# Sheet2.net
KiCad netlist of a schematic drawn in Altium Designer
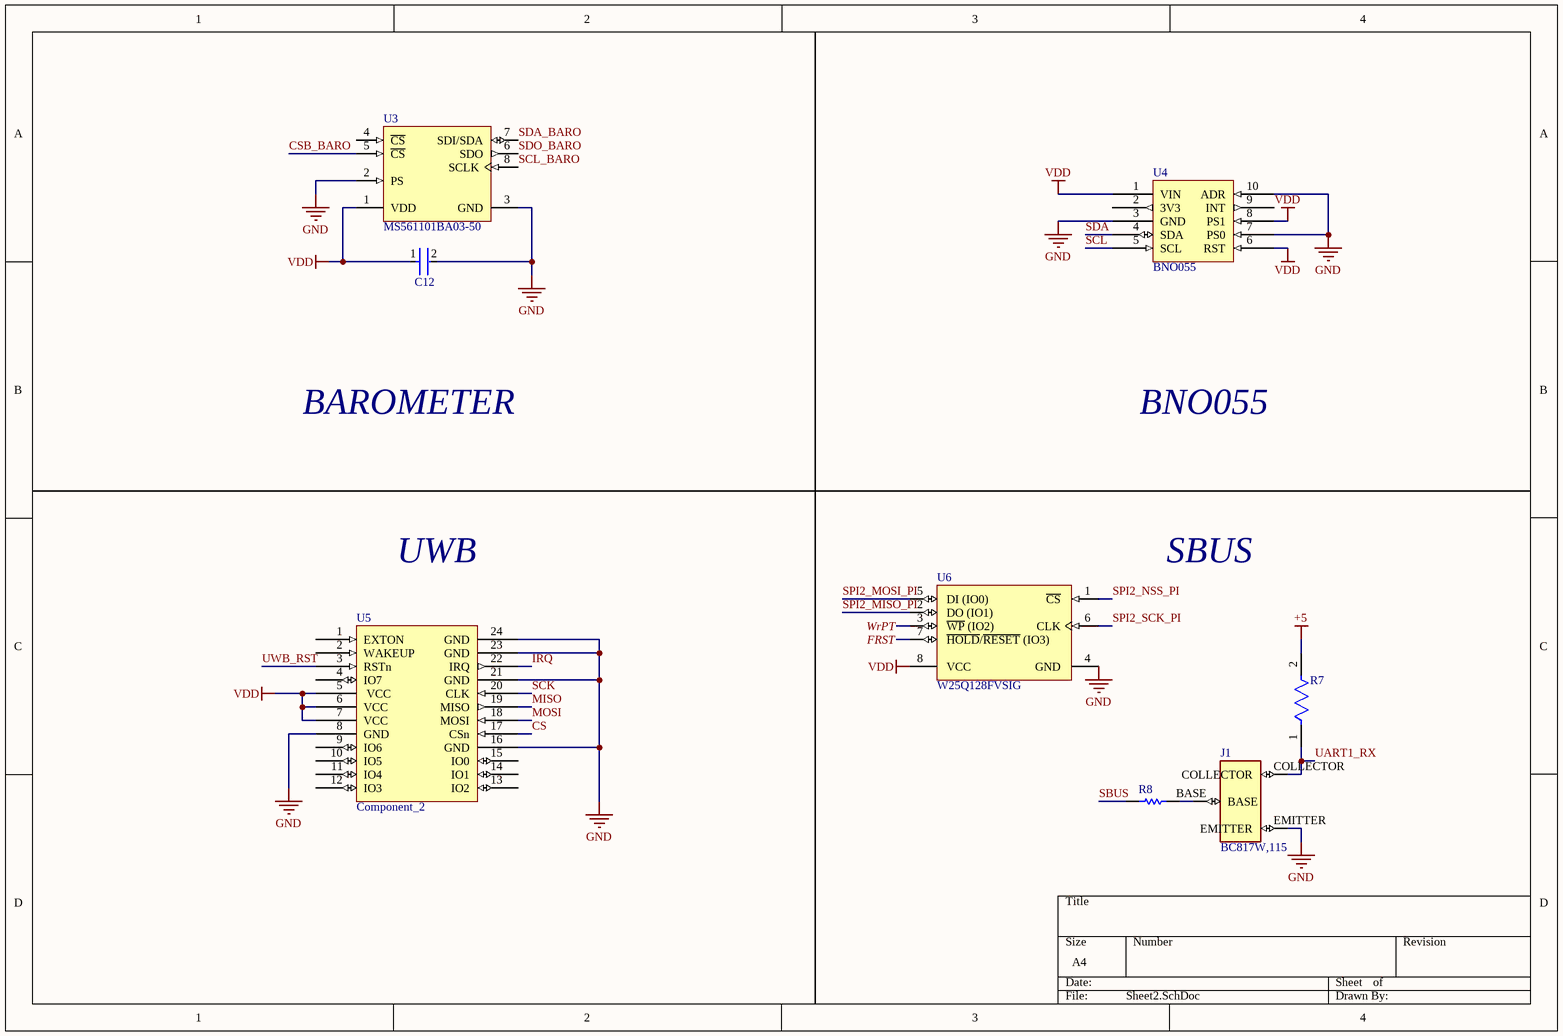
[diagram p0: Sheet2.SchDoc]

(export (version "E")
  (design (tool "Eeschema 10.0.6"))
  (components
    (comp (ref "C12")
      (value "C0603C104K4RACTU")
      (footprint "FP-C0603C-CF-MFG")
      (description "Capacitor; Ceramic; Cap; .100uF; Tol 10%; SMT; Vol-Rtg 16V; X7R; Tape and Reel")
      (fields
        (field (name "OCTOPART") "https://octopart.com/c0603c104k4ractu-kemet-93067")
        (field (name "MANUFACTURER") "KEMET")
      )
      (libsource (lib "Altium Content Vault") (part "b4654b650e69147ec39a6b967a45e02"))
    )
    (comp (ref "J1")
      (value "BC817W,115")
      (footprint "SOT323")
      (description "Bipolar (BJT) Transistor NPN 45 V 500 mA 100MHz 200 mW Surface Mount SOT-323")
      (fields (field (name "MF") "Nexperia USA"))
      (libsource (lib "BC817W,115") (part "BC817W,115"))
    )
    (comp (ref "R7")
      (value "MCT06030C1002FP500")
      (footprint "FP-MCT0603-IPC_C")
      (description "RES SMD 100 OHM 1% 1/8W 0603")
      (fields (field (name "TOLERANCE") "1%"))
      (libsource (lib "Altium Content Vault") (part "1029c3af85768c4190bb7ad29bc67b5"))
    )
    (comp (ref "R8")
      (value "RC0603JR-074K7L")
      (footprint "RESC1608X55X25ML10T15")
      (description "Chip Resistor, 4.7 KOhm, +/- 5%, 100 mW, -55 to 155 degC, 0603 (1608 Metric), RoHS, Tape and Reel")
      (fields (field (name "TOLERANCE") "5%") (field (name "MANUFACTURER") "Yageo"))
      (libsource (lib "Altium Content Vault") (part "RES-2"))
    )
    (comp (ref "U3")
      (value "MS561101BA03-50")
      (footprint "MSI-MS561101BA03-50-8_V")
      (fields (field (name "MANUFACTURER") "Measurement Specialties"))
      (libsource (lib "Altium Content Vault") (part "MSI-MS561101BA03-50-8"))
    )
    (comp (ref "U4")
      (value "BNO055")
      (footprint "BNO055_MOD")
      (libsource (lib "BNO055") (part "Component_1"))
    )
    (comp (ref "U5")
      (value "Component_2")
      (footprint "BU01")
      (libsource (lib "BU01 UWB") (part "Component_2"))
    )
    (comp (ref "U6")
      (value "W25Q128FVSIG")
      (footprint "WINB-SOIC-8_M")
      (fields (field (name "MANUFACTURER") "Winbond"))
      (libsource (lib "Altium Content Vault") (part "WINB-W25Q128FVSIG-SOIC-8"))
    )
  )
  (nets
    (net (code "1") (name "+5") (class "Default")
      (node (ref "R7") (pin "2") (pinfunction "2_2") (pintype "passive"))
    )
    (net (code "2") (name "/CS") (class "Default")
      (node (ref "U5") (pin "17") (pinfunction "CSn_17") (pintype "input"))
    )
    (net (code "3") (name "/CSB_BARO") (class "Default")
      (node (ref "U3") (pin "5") (pinfunction "~{CS}_5") (pintype "input"))
    )
    (net (code "4") (name "/FRST") (class "Default")
      (node (ref "U6") (pin "7") (pinfunction "~{HOLD}/~{RESET}_(IO3)_7") (pintype "bidirectional"))
    )
    (net (code "5") (name "/IRQ") (class "Default")
      (node (ref "U5") (pin "22") (pinfunction "IRQ_22") (pintype "output"))
    )
    (net (code "6") (name "/MISO") (class "Default")
      (node (ref "U5") (pin "19") (pinfunction "MISO_19") (pintype "output"))
    )
    (net (code "7") (name "/MOSI") (class "Default")
      (node (ref "U5") (pin "18") (pinfunction "MOSI_18") (pintype "input"))
    )
    (net (code "8") (name "/SBUS") (class "Default")
      (node (ref "R8") (pin "1") (pinfunction "1_1") (pintype "passive"))
    )
    (net (code "9") (name "/SCK") (class "Default")
      (node (ref "U5") (pin "20") (pinfunction "CLK_20") (pintype "input"))
    )
    (net (code "10") (name "/SCL") (class "Default")
      (node (ref "U4") (pin "5") (pinfunction "SCL_5") (pintype "input"))
    )
    (net (code "11") (name "/SCL_BARO") (class "Default")
      (node (ref "U3") (pin "8") (pinfunction "SCLK_8") (pintype "input"))
    )
    (net (code "12") (name "/SDA") (class "Default")
      (node (ref "U4") (pin "4") (pinfunction "SDA_4") (pintype "bidirectional"))
    )
    (net (code "13") (name "/SDA_BARO") (class "Default")
      (node (ref "U3") (pin "7") (pinfunction "SDI/SDA_7") (pintype "bidirectional"))
    )
    (net (code "14") (name "/SDO_BARO") (class "Default")
      (node (ref "U3") (pin "6") (pinfunction "SDO_6") (pintype "output"))
    )
    (net (code "15") (name "/SPI2_MISO_PI") (class "Default")
      (node (ref "U6") (pin "2") (pinfunction "DO_(IO1)_2") (pintype "bidirectional"))
    )
    (net (code "16") (name "/SPI2_MOSI_PI") (class "Default")
      (node (ref "U6") (pin "5") (pinfunction "DI_(IO0)_5") (pintype "bidirectional"))
    )
    (net (code "17") (name "/SPI2_NSS_PI") (class "Default")
      (node (ref "U6") (pin "1") (pinfunction "~{CS}_1") (pintype "input"))
    )
    (net (code "18") (name "/SPI2_SCK_PI") (class "Default")
      (node (ref "U6") (pin "6") (pinfunction "CLK_6") (pintype "input"))
    )
    (net (code "19") (name "/UART1_RX") (class "Default")
      (node (ref "J1") (pin "COLLECTOR") (pinfunction "COLLECTOR_COLLECTOR") (pintype "bidirectional"))
      (node (ref "R7") (pin "1") (pinfunction "1_1") (pintype "passive"))
    )
    (net (code "20") (name "/UWB_RST") (class "Default")
      (node (ref "U5") (pin "3") (pinfunction "RSTn_3") (pintype "input"))
    )
    (net (code "21") (name "/WrPT") (class "Default")
      (node (ref "U6") (pin "3") (pinfunction "~{WP}_(IO2)_3") (pintype "bidirectional"))
    )
    (net (code "22") (name "GND") (class "Default")
      (node (ref "C12") (pin "2") (pinfunction "2_2") (pintype "passive"))
      (node (ref "J1") (pin "EMITTER") (pinfunction "EMITTER_EMITTER") (pintype "bidirectional"))
      (node (ref "U3") (pin "2") (pinfunction "PS_2") (pintype "input"))
      (node (ref "U3") (pin "3") (pinfunction "GND_3") (pintype "power_in"))
      (node (ref "U4") (pin "10") (pinfunction "ADR_10") (pintype "input"))
      (node (ref "U4") (pin "3") (pinfunction "GND_3") (pintype "power_in"))
      (node (ref "U4") (pin "7") (pinfunction "PS0_7") (pintype "input"))
      (node (ref "U5") (pin "16") (pinfunction "GND_16") (pintype "power_in"))
      (node (ref "U5") (pin "21") (pinfunction "GND_21") (pintype "power_in"))
      (node (ref "U5") (pin "23") (pinfunction "GND_23") (pintype "power_in"))
      (node (ref "U5") (pin "24") (pinfunction "GND_24") (pintype "power_in"))
      (node (ref "U5") (pin "8") (pinfunction "GND_8") (pintype "power_in"))
      (node (ref "U6") (pin "4") (pinfunction "GND_4") (pintype "power_in"))
    )
    (net (code "23") (name "Net-(J1-PadBASE)") (class "Default")
      (node (ref "J1") (pin "BASE") (pinfunction "BASE_BASE") (pintype "bidirectional"))
      (node (ref "R8") (pin "2") (pinfunction "2_2") (pintype "passive"))
    )
    (net (code "24") (name "VDD") (class "Default")
      (node (ref "C12") (pin "1") (pinfunction "1_1") (pintype "passive"))
      (node (ref "U3") (pin "1") (pinfunction "VDD_1") (pintype "power_in"))
      (node (ref "U4") (pin "1") (pinfunction "VIN_1") (pintype "power_in"))
      (node (ref "U4") (pin "6") (pinfunction "RST_6") (pintype "input"))
      (node (ref "U4") (pin "8") (pinfunction "PS1_8") (pintype "input"))
      (node (ref "U5") (pin "5") (pinfunction "_VCC_5") (pintype "power_in"))
      (node (ref "U5") (pin "6") (pinfunction "VCC_6") (pintype "power_in"))
      (node (ref "U5") (pin "7") (pinfunction "VCC_7") (pintype "power_in"))
      (node (ref "U6") (pin "8") (pinfunction "VCC_8") (pintype "power_in"))
    )
    (net (code "25") (name "unconnected-(U3-~{CS}-Pad4)") (class "Default")
      (node (ref "U3") (pin "4") (pinfunction "~{CS}_4") (pintype "input"))
    )
    (net (code "26") (name "unconnected-(U4-3V3-Pad2)") (class "Default")
      (node (ref "U4") (pin "2") (pinfunction "3V3_2") (pintype "output"))
    )
    (net (code "27") (name "unconnected-(U4-INT-Pad9)") (class "Default")
      (node (ref "U4") (pin "9") (pinfunction "INT_9") (pintype "output"))
    )
    (net (code "28") (name "unconnected-(U5-EXTON-Pad1)") (class "Default")
      (node (ref "U5") (pin "1") (pinfunction "EXTON_1") (pintype "input"))
    )
    (net (code "29") (name "unconnected-(U5-IO0-Pad15)") (class "Default")
      (node (ref "U5") (pin "15") (pinfunction "IO0_15") (pintype "bidirectional"))
    )
    (net (code "30") (name "unconnected-(U5-IO1-Pad14)") (class "Default")
      (node (ref "U5") (pin "14") (pinfunction "IO1_14") (pintype "bidirectional"))
    )
    (net (code "31") (name "unconnected-(U5-IO2-Pad13)") (class "Default")
      (node (ref "U5") (pin "13") (pinfunction "IO2_13") (pintype "bidirectional"))
    )
    (net (code "32") (name "unconnected-(U5-IO3-Pad12)") (class "Default")
      (node (ref "U5") (pin "12") (pinfunction "IO3_12") (pintype "bidirectional"))
    )
    (net (code "33") (name "unconnected-(U5-IO4-Pad11)") (class "Default")
      (node (ref "U5") (pin "11") (pinfunction "IO4_11") (pintype "bidirectional"))
    )
    (net (code "34") (name "unconnected-(U5-IO5-Pad10)") (class "Default")
      (node (ref "U5") (pin "10") (pinfunction "IO5_10") (pintype "bidirectional"))
    )
    (net (code "35") (name "unconnected-(U5-IO6-Pad9)") (class "Default")
      (node (ref "U5") (pin "9") (pinfunction "IO6_9") (pintype "bidirectional"))
    )
    (net (code "36") (name "unconnected-(U5-IO7-Pad4)") (class "Default")
      (node (ref "U5") (pin "4") (pinfunction "IO7_4") (pintype "bidirectional"))
    )
    (net (code "37") (name "unconnected-(U5-WAKEUP-Pad2)") (class "Default")
      (node (ref "U5") (pin "2") (pinfunction "WAKEUP_2") (pintype "input"))
    )
  )
)
